# Andranik_Lab2_Schem.net
KiCad netlist of a schematic drawn in EAGLE
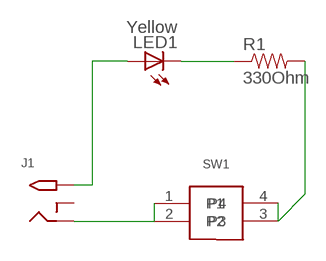
[diagram p0: schematic, sheet 1]

(export (version "E")
  (design (tool "Eeschema 10.0.6"))
  (components
    (comp (ref "J1")
      (value "2.1MMJACKTHM")
      (footprint "eagle-import:PJ-102A")
      (libsource (lib "eagle-import") (part "2.1MMJACKTHM"))
    )
    (comp (ref "LED1")
      (value "Yellow")
      (footprint "eagle-import:LED5MM")
      (libsource (lib "eagle-import") (part "LED5MM"))
    )
    (comp (ref "R1")
      (value "330Ohm")
      (footprint "eagle-import:AXIAL-0.3")
      (libsource (lib "eagle-import") (part "RESISTORAXIAL-0.3"))
    )
    (comp (ref "SW1")
      (value "BUTTON-TACTILE-SQUARE")
      (footprint "eagle-import:BUTTON-TACTILE-SQUARE")
      (libsource (lib "eagle-import") (part "BUTTON-TACTILE-SQUARE"))
    )
  )
  (nets
    (net (code "1") (name "Net-(J1-PadTIP)") (class "Default")
      (node (ref "J1") (pin "TIP") (pinfunction "TIP_TIP") (pintype "bidirectional"))
      (node (ref "LED1") (pin "A") (pinfunction "A_A") (pintype "passive"))
    )
    (net (code "2") (name "Net-(LED1-C)") (class "Default")
      (node (ref "LED1") (pin "K") (pinfunction "C_K") (pintype "passive"))
      (node (ref "R1") (pin "P$1") (pinfunction "1_P$1") (pintype "passive"))
    )
    (net (code "3") (name "Net-(R1-2)") (class "Default")
      (node (ref "R1") (pin "P$2") (pinfunction "2_P$2") (pintype "passive"))
      (node (ref "SW1") (pin "3") (pinfunction "P3_3") (pintype "bidirectional"))
      (node (ref "SW1") (pin "4") (pinfunction "P4_4") (pintype "bidirectional"))
    )
    (net (code "4") (name "Net-(SW1-P1)") (class "Default")
      (node (ref "J1") (pin "RING") (pinfunction "RING_RING") (pintype "bidirectional"))
      (node (ref "SW1") (pin "1") (pinfunction "P1_1") (pintype "bidirectional"))
      (node (ref "SW1") (pin "2") (pinfunction "P2_2") (pintype "bidirectional"))
    )
    (net (code "5") (name "unconnected-(J1-PadRING_SW)") (class "Default")
      (node (ref "J1") (pin "RING_SW") (pinfunction "RING_SW_RING_SW") (pintype "bidirectional"))
    )
  )
)
